# lv_2.net
KiCad netlist of a schematic drawn in Altium Designer
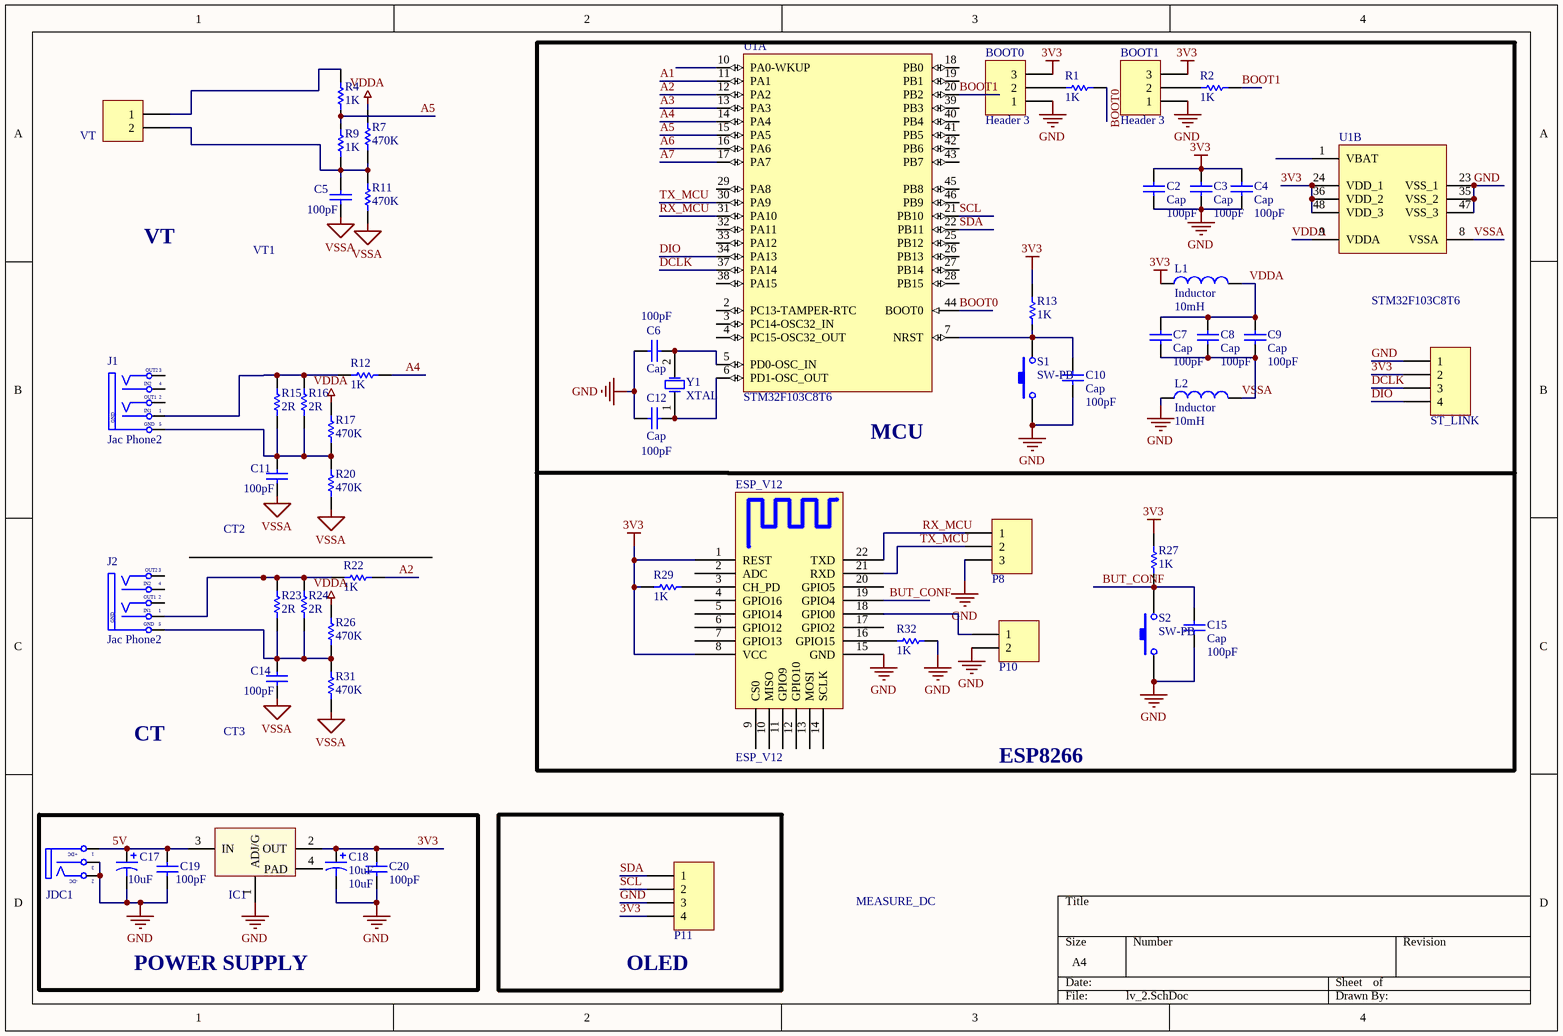
[diagram p0: lv_2.SchDoc]

(export (version "E")
  (design (tool "Eeschema 10.0.6"))
  (components
    (comp (ref "BOOT0")
      (value "Header 3")
      (footprint "JP3")
      (description "Header, 3-Pin")
      (fields (field (name "PUBLISHER") "Altium Limited"))
      (libsource (lib "Miscellaneous Connectors") (part "Header 3"))
    )
    (comp (ref "BOOT1")
      (value "Header 3")
      (footprint "JP3")
      (description "Header, 3-Pin")
      (fields (field (name "PUBLISHER") "Altium Limited"))
      (libsource (lib "Miscellaneous Connectors") (part "Header 3"))
    )
    (comp (ref "C2")
      (value "Cap")
      (footprint "CAP-SM-0603")
      (description "Capacitor")
      (fields (field (name "ALTIUM_VALUE") "100pF") (field (name "PUBLISHER") "Altium Limited"))
      (libsource (lib "Miscellaneous Devices") (part "Cap"))
    )
    (comp (ref "C3")
      (value "Cap")
      (footprint "CAP-SM-0603")
      (description "Capacitor")
      (fields (field (name "ALTIUM_VALUE") "100pF") (field (name "PUBLISHER") "Altium Limited"))
      (libsource (lib "Miscellaneous Devices") (part "Cap"))
    )
    (comp (ref "C4")
      (value "Cap")
      (footprint "CAP-SM-0603")
      (description "Capacitor")
      (fields (field (name "ALTIUM_VALUE") "100pF") (field (name "PUBLISHER") "Altium Limited"))
      (libsource (lib "Miscellaneous Devices") (part "Cap"))
    )
    (comp (ref "C5")
      (value "100pF")
      (footprint "CAP-SM-0603")
      (description "Capacitor")
      (fields (field (name "Comment") "Cap Non-Pol SMD"))
      (libsource (lib "PIF_Library") (part "Cap Non-Pol SMD"))
    )
    (comp (ref "C6")
      (value "Cap")
      (footprint "CAP-SM-0603")
      (description "Capacitor")
      (fields (field (name "ALTIUM_VALUE") "100pF") (field (name "PUBLISHER") "Altium Limited"))
      (libsource (lib "Miscellaneous Devices") (part "Cap"))
    )
    (comp (ref "C7")
      (value "Cap")
      (footprint "CAP-SM-0603")
      (description "Capacitor")
      (fields (field (name "ALTIUM_VALUE") "100pF") (field (name "PUBLISHER") "Altium Limited"))
      (libsource (lib "Miscellaneous Devices") (part "Cap"))
    )
    (comp (ref "C8")
      (value "Cap")
      (footprint "CAP-SM-0603")
      (description "Capacitor")
      (fields (field (name "ALTIUM_VALUE") "100pF") (field (name "PUBLISHER") "Altium Limited"))
      (libsource (lib "Miscellaneous Devices") (part "Cap"))
    )
    (comp (ref "C9")
      (value "Cap")
      (footprint "CAP-SM-0603")
      (description "Capacitor")
      (fields (field (name "ALTIUM_VALUE") "100pF") (field (name "PUBLISHER") "Altium Limited"))
      (libsource (lib "Miscellaneous Devices") (part "Cap"))
    )
    (comp (ref "C10")
      (value "Cap")
      (footprint "CAP-SM-0603")
      (description "Capacitor")
      (fields (field (name "ALTIUM_VALUE") "100pF") (field (name "PUBLISHER") "Altium Limited"))
      (libsource (lib "Miscellaneous Devices") (part "Cap"))
    )
    (comp (ref "C11")
      (value "100pF")
      (footprint "CAP-SM-0603")
      (description "Capacitor")
      (fields (field (name "Comment") "Cap Non-Pol SMD"))
      (libsource (lib "PIF_Library") (part "Cap Non-Pol SMD"))
    )
    (comp (ref "C12")
      (value "Cap")
      (footprint "CAP-SM-0603")
      (description "Capacitor")
      (fields (field (name "ALTIUM_VALUE") "100pF") (field (name "PUBLISHER") "Altium Limited"))
      (libsource (lib "Miscellaneous Devices") (part "Cap"))
    )
    (comp (ref "C14")
      (value "100pF")
      (footprint "CAP-SM-0603")
      (description "Capacitor")
      (fields (field (name "Comment") "Cap Non-Pol SMD"))
      (libsource (lib "PIF_Library") (part "Cap Non-Pol SMD"))
    )
    (comp (ref "C15")
      (value "Cap")
      (footprint "CAP-SM-0603")
      (description "Capacitor")
      (fields (field (name "ALTIUM_VALUE") "100pF") (field (name "PUBLISHER") "Altium Limited"))
      (libsource (lib "Miscellaneous Devices") (part "Cap"))
    )
    (comp (ref "C17")
      (value "10uF")
      (footprint "CP1/2")
      (description "Polarized Capacitor (Radial)")
      (fields (field (name "PUBLISHER") "Altium Limited"))
      (libsource (lib "Miscellaneous Devices") (part "Cap Pol1"))
    )
    (comp (ref "C18")
      (value "10uF")
      (footprint "CP1/2")
      (description "Polarized Capacitor (Radial)")
      (fields (field (name "ALTIUM_VALUE") "10uF") (field (name "PUBLISHER") "Altium Limited"))
      (libsource (lib "Miscellaneous Devices") (part "Cap Pol1"))
    )
    (comp (ref "C19")
      (value "100pF")
      (footprint "CAP-SM-0603")
      (description "Capacitor")
      (fields (field (name "Comment") "Cap Non-Pol SMD"))
      (libsource (lib "PIF_Library") (part "Cap Non-Pol SMD"))
    )
    (comp (ref "C20")
      (value "100pF")
      (footprint "CAP-SM-0603")
      (description "Capacitor")
      (fields (field (name "Comment") "Cap Non-Pol SMD"))
      (libsource (lib "PIF_Library") (part "Cap Non-Pol SMD"))
    )
    (comp (ref "ESP_V12")
      (value "ESP_V12")
      (footprint "ESP_12_E")
      (libsource (lib "espv12") (part "Component_1"))
    )
    (comp (ref "IC1")
      (value "LM1117")
      (footprint "SOT223-4N")
      (description "Available in 1.8V, 2.5V, 2.85V, 3.3V, 5V, and  Adjustable Versions")
      (libsource (lib "PIF_Library") (part "LM1117"))
    )
    (comp (ref "J1")
      (value "Jac Phone2")
      (footprint "JacPhone2")
      (description "Jac Phone Stereo")
      (fields (field (name "CREAT BY") "VanDungEvn@Gmail.com"))
      (libsource (lib "syhaunguyen") (part "Jac Phone2"))
    )
    (comp (ref "J2")
      (value "Jac Phone2")
      (footprint "JacPhone2")
      (description "Jac Phone Stereo")
      (fields (field (name "CREAT BY") "VanDungEvn@Gmail.com"))
      (libsource (lib "syhaunguyen") (part "Jac Phone2"))
    )
    (comp (ref "JDC1")
      (value "Jack DC")
      (footprint "DC-IN")
      (description "Jack DC input")
      (libsource (lib "PIF_Library") (part "Jack DC"))
    )
    (comp (ref "L1")
      (value "Inductor")
      (footprint "CAP-SM-0603")
      (fields (field (name "ALTIUM_VALUE") "10mH") (field (name "PUBLISHER") "Altium Limited"))
      (libsource (lib "Miscellaneous Devices") (part "Inductor"))
    )
    (comp (ref "L2")
      (value "Inductor")
      (footprint "CAP-SM-0603")
      (fields (field (name "ALTIUM_VALUE") "10mH") (field (name "PUBLISHER") "Altium Limited"))
      (libsource (lib "Miscellaneous Devices") (part "Inductor"))
    )
    (comp (ref "P8")
      (value "Header 3")
      (footprint "JP3")
      (description "Header, 3-Pin")
      (fields (field (name "PUBLISHER") "Altium Limited"))
      (libsource (lib "PIF_Library") (part "Header 3"))
    )
    (comp (ref "P10")
      (value "Header 2")
      (footprint "JP2")
      (description "Header, 2-Pin")
      (fields (field (name "PUBLISHER") "Altium Limited"))
      (libsource (lib "PIF_Library") (part "Header 2"))
    )
    (comp (ref "P11")
      (value "Header 4")
      (footprint "JP4")
      (description "Header, 4-Pin")
      (fields (field (name "PUBLISHER") "Altium Limited"))
      (libsource (lib "PIF_Library") (part "Header 4"))
    )
    (comp (ref "R1")
      (value "1K")
      (footprint "RES-SM-0603")
      (description "Resistor")
      (fields (field (name "Comment") "RESISTOR SMD"))
      (libsource (lib "PIF_Library") (part "RESISTOR SMD"))
    )
    (comp (ref "R2")
      (value "1K")
      (footprint "RES-SM-0603")
      (description "Resistor")
      (fields (field (name "Comment") "RESISTOR SMD"))
      (libsource (lib "PIF_Library") (part "RESISTOR SMD"))
    )
    (comp (ref "R4")
      (value "1K")
      (footprint "RES-SM-0603")
      (description "Resistor")
      (libsource (lib "PIF_Library") (part "RESISTOR SMD"))
    )
    (comp (ref "R7")
      (value "470K")
      (footprint "RES-SM-0603")
      (description "Resistor")
      (libsource (lib "PIF_Library") (part "RESISTOR SMD"))
    )
    (comp (ref "R9")
      (value "1K")
      (footprint "RES-SM-0603")
      (description "Resistor")
      (libsource (lib "PIF_Library") (part "RESISTOR SMD"))
    )
    (comp (ref "R11")
      (value "470K")
      (footprint "RES-SM-0603")
      (description "Resistor")
      (libsource (lib "PIF_Library") (part "RESISTOR SMD"))
    )
    (comp (ref "R12")
      (value "1K")
      (footprint "RES-SM-0603")
      (description "Resistor")
      (fields (field (name "Comment") "RESISTOR SMD"))
      (libsource (lib "PIF_Library") (part "RESISTOR SMD"))
    )
    (comp (ref "R13")
      (value "1K")
      (footprint "RES-SM-0603")
      (description "Resistor")
      (fields (field (name "Comment") "RESISTOR SMD"))
      (libsource (lib "PIF_Library") (part "RESISTOR SMD"))
    )
    (comp (ref "R15")
      (value "2R")
      (footprint "RES-SM-0603")
      (description "Resistor")
      (fields (field (name "Comment") "RESISTOR SMD"))
      (libsource (lib "PIF_Library") (part "RESISTOR SMD"))
    )
    (comp (ref "R16")
      (value "2R")
      (footprint "RES-SM-0603")
      (description "Resistor")
      (fields (field (name "Comment") "RESISTOR SMD"))
      (libsource (lib "PIF_Library") (part "RESISTOR SMD"))
    )
    (comp (ref "R17")
      (value "470K")
      (footprint "RES-SM-0603")
      (description "Resistor")
      (fields (field (name "Comment") "RESISTOR SMD"))
      (libsource (lib "PIF_Library") (part "RESISTOR SMD"))
    )
    (comp (ref "R20")
      (value "470K")
      (footprint "RES-SM-0603")
      (description "Resistor")
      (fields (field (name "Comment") "RESISTOR SMD"))
      (libsource (lib "PIF_Library") (part "RESISTOR SMD"))
    )
    (comp (ref "R22")
      (value "1K")
      (footprint "RES-SM-0603")
      (description "Resistor")
      (fields (field (name "Comment") "RESISTOR SMD"))
      (libsource (lib "PIF_Library") (part "RESISTOR SMD"))
    )
    (comp (ref "R23")
      (value "2R")
      (footprint "RES-SM-0603")
      (description "Resistor")
      (fields (field (name "Comment") "RESISTOR SMD"))
      (libsource (lib "PIF_Library") (part "RESISTOR SMD"))
    )
    (comp (ref "R24")
      (value "2R")
      (footprint "RES-SM-0603")
      (description "Resistor")
      (fields (field (name "Comment") "RESISTOR SMD"))
      (libsource (lib "PIF_Library") (part "RESISTOR SMD"))
    )
    (comp (ref "R26")
      (value "470K")
      (footprint "RES-SM-0603")
      (description "Resistor")
      (fields (field (name "Comment") "RESISTOR SMD"))
      (libsource (lib "PIF_Library") (part "RESISTOR SMD"))
    )
    (comp (ref "R27")
      (value "1K")
      (footprint "RES-SM-0603")
      (description "Resistor")
      (fields (field (name "Comment") "RESISTOR SMD"))
      (libsource (lib "PIF_Library") (part "RESISTOR SMD"))
    )
    (comp (ref "R29")
      (value "1K")
      (footprint "RES-SM-0603")
      (description "Resistor")
      (fields (field (name "Comment") "RESISTOR SMD"))
      (libsource (lib "PIF_Library") (part "RESISTOR SMD"))
    )
    (comp (ref "R31")
      (value "470K")
      (footprint "RES-SM-0603")
      (description "Resistor")
      (fields (field (name "Comment") "RESISTOR SMD"))
      (libsource (lib "PIF_Library") (part "RESISTOR SMD"))
    )
    (comp (ref "R32")
      (value "1K")
      (footprint "RES-SM-0603")
      (description "Resistor")
      (fields (field (name "Comment") "RESISTOR SMD"))
      (libsource (lib "PIF_Library") (part "RESISTOR SMD"))
    )
    (comp (ref "S1")
      (value "SW-PB")
      (footprint "Tact SW 4 pin")
      (description "Switch")
      (fields (field (name "PUBLISHER") "Altium Limited"))
      (libsource (lib "Miscellaneous Devices") (part "SW-PB"))
    )
    (comp (ref "S2")
      (value "SW-PB")
      (footprint "Tact SW 4 pin")
      (description "Switch")
      (fields (field (name "PUBLISHER") "Altium Limited"))
      (libsource (lib "Miscellaneous Devices") (part "SW-PB"))
    )
    (comp (ref "ST_LINK")
      (value "Header 4")
      (footprint "JP4")
      (description "Header, 4-Pin")
      (fields (field (name "PUBLISHER") "Altium Limited"))
      (libsource (lib "PIF_Schematic_Lib") (part "Header 4"))
    )
    (comp (ref "U1")
      (value "STM32F103C8T6")
      (footprint "STM-LQFP48_L")
      (libsource (lib "STMicroelectronics STM32 F1") (part "STM32F103C8T6"))
    )
    (comp (ref "VT")
      (value "Domino 2")
      (footprint "DOMINO 2- 5mm")
      (description "Domino, 2-Pin")
      (fields (field (name "PUBLISHER") "Altium Limited"))
      (libsource (lib "PIF_Library") (part "Domino 2"))
    )
    (comp (ref "Y1")
      (value "XTAL")
      (footprint "XT2")
      (description "Crystal Oscillator")
      (fields (field (name "PUBLISHER") "Altium Limited"))
      (libsource (lib "Miscellaneous Devices") (part "XTAL"))
    )
  )
  (nets
    (net (code "1") (name "/5V") (class "Default")
      (node (ref "C17") (pin "1") (pinfunction "1_1") (pintype "passive"))
      (node (ref "C19") (pin "2") (pinfunction "2_2") (pintype "passive"))
      (node (ref "IC1") (pin "3") (pinfunction "IN_3") (pintype "passive"))
      (node (ref "JDC1") (pin "1") (pinfunction "T_1") (pintype "passive"))
    )
    (net (code "2") (name "/A1") (class "Default")
      (node (ref "U1") (pin "11") (pinfunction "PA1_11") (pintype "bidirectional"))
    )
    (net (code "3") (name "/A2") (class "Default")
      (node (ref "R22") (pin "1") (pinfunction "1_1") (pintype "passive"))
      (node (ref "U1") (pin "12") (pinfunction "PA2_12") (pintype "bidirectional"))
    )
    (net (code "4") (name "/A3") (class "Default")
      (node (ref "U1") (pin "13") (pinfunction "PA3_13") (pintype "bidirectional"))
    )
    (net (code "5") (name "/A4") (class "Default")
      (node (ref "R12") (pin "1") (pinfunction "1_1") (pintype "passive"))
      (node (ref "U1") (pin "14") (pinfunction "PA4_14") (pintype "bidirectional"))
    )
    (net (code "6") (name "/A5") (class "Default")
      (node (ref "R4") (pin "1") (pinfunction "1_1") (pintype "passive"))
      (node (ref "R9") (pin "2") (pinfunction "2_2") (pintype "passive"))
      (node (ref "U1") (pin "15") (pinfunction "PA5_15") (pintype "bidirectional"))
    )
    (net (code "7") (name "/A6") (class "Default")
      (node (ref "U1") (pin "16") (pinfunction "PA6_16") (pintype "bidirectional"))
    )
    (net (code "8") (name "/A7") (class "Default")
      (node (ref "U1") (pin "17") (pinfunction "PA7_17") (pintype "bidirectional"))
    )
    (net (code "9") (name "/BOOT0") (class "Default")
      (node (ref "R1") (pin "1") (pinfunction "1_1") (pintype "passive"))
      (node (ref "U1") (pin "44") (pinfunction "BOOT0_44") (pintype "input"))
    )
    (net (code "10") (name "/BOOT1") (class "Default")
      (node (ref "R2") (pin "1") (pinfunction "1_1") (pintype "passive"))
      (node (ref "U1") (pin "20") (pinfunction "PB2_20") (pintype "bidirectional"))
    )
    (net (code "11") (name "/BUT_CONF") (class "Default")
      (node (ref "C15") (pin "2") (pinfunction "2_2") (pintype "passive"))
      (node (ref "ESP_V12") (pin "19") (pinfunction "GPIO4_19") (pintype "passive"))
      (node (ref "R27") (pin "2") (pinfunction "2_2") (pintype "passive"))
      (node (ref "S2") (pin "2") (pinfunction "2_2") (pintype "passive"))
    )
    (net (code "12") (name "/DCLK") (class "Default")
      (node (ref "ST_LINK") (pin "3") (pinfunction "3_3") (pintype "passive"))
      (node (ref "U1") (pin "37") (pinfunction "PA14_37") (pintype "bidirectional"))
    )
    (net (code "13") (name "/DIO") (class "Default")
      (node (ref "ST_LINK") (pin "4") (pinfunction "4_4") (pintype "passive"))
      (node (ref "U1") (pin "34") (pinfunction "PA13_34") (pintype "bidirectional"))
    )
    (net (code "14") (name "/RX_MCU") (class "Default")
      (node (ref "ESP_V12") (pin "22") (pinfunction "TXD_22") (pintype "passive"))
      (node (ref "P8") (pin "1") (pinfunction "1_1") (pintype "passive"))
      (node (ref "U1") (pin "31") (pinfunction "PA10_31") (pintype "bidirectional"))
    )
    (net (code "15") (name "/SCL") (class "Default")
      (node (ref "P11") (pin "2") (pinfunction "2_2") (pintype "passive"))
      (node (ref "U1") (pin "21") (pinfunction "PB10_21") (pintype "bidirectional"))
    )
    (net (code "16") (name "/SDA") (class "Default")
      (node (ref "P11") (pin "1") (pinfunction "1_1") (pintype "passive"))
      (node (ref "U1") (pin "22") (pinfunction "PB11_22") (pintype "bidirectional"))
    )
    (net (code "17") (name "/TX_MCU") (class "Default")
      (node (ref "ESP_V12") (pin "21") (pinfunction "RXD_21") (pintype "passive"))
      (node (ref "P8") (pin "2") (pinfunction "2_2") (pintype "passive"))
      (node (ref "U1") (pin "30") (pinfunction "PA9_30") (pintype "bidirectional"))
    )
    (net (code "18") (name "3V3") (class "Default")
      (node (ref "BOOT0") (pin "3") (pinfunction "3_3") (pintype "passive"))
      (node (ref "BOOT1") (pin "3") (pinfunction "3_3") (pintype "passive"))
      (node (ref "C18") (pin "1") (pinfunction "1_1") (pintype "passive"))
      (node (ref "C2") (pin "2") (pinfunction "2_2") (pintype "passive"))
      (node (ref "C20") (pin "2") (pinfunction "2_2") (pintype "passive"))
      (node (ref "C3") (pin "2") (pinfunction "2_2") (pintype "passive"))
      (node (ref "C4") (pin "2") (pinfunction "2_2") (pintype "passive"))
      (node (ref "ESP_V12") (pin "1") (pinfunction "REST_1") (pintype "passive"))
      (node (ref "ESP_V12") (pin "8") (pinfunction "VCC_8") (pintype "passive"))
      (node (ref "IC1") (pin "2") (pinfunction "OUT_2") (pintype "passive"))
      (node (ref "L1") (pin "1") (pinfunction "1_1") (pintype "passive"))
      (node (ref "P11") (pin "4") (pinfunction "4_4") (pintype "passive"))
      (node (ref "R13") (pin "1") (pinfunction "1_1") (pintype "passive"))
      (node (ref "R27") (pin "1") (pinfunction "1_1") (pintype "passive"))
      (node (ref "R29") (pin "1") (pinfunction "1_1") (pintype "passive"))
      (node (ref "ST_LINK") (pin "2") (pinfunction "2_2") (pintype "passive"))
      (node (ref "U1") (pin "24") (pinfunction "VDD_1_24") (pintype "power_in"))
      (node (ref "U1") (pin "36") (pinfunction "VDD_2_36") (pintype "power_in"))
      (node (ref "U1") (pin "48") (pinfunction "VDD_3_48") (pintype "power_in"))
    )
    (net (code "19") (name "GND") (class "Default")
      (node (ref "BOOT0") (pin "1") (pinfunction "1_1") (pintype "passive"))
      (node (ref "BOOT1") (pin "1") (pinfunction "1_1") (pintype "passive"))
      (node (ref "C10") (pin "1") (pinfunction "1_1") (pintype "passive"))
      (node (ref "C12") (pin "1") (pinfunction "1_1") (pintype "passive"))
      (node (ref "C15") (pin "1") (pinfunction "1_1") (pintype "passive"))
      (node (ref "C17") (pin "2") (pinfunction "2_2") (pintype "passive"))
      (node (ref "C18") (pin "2") (pinfunction "2_2") (pintype "passive"))
      (node (ref "C19") (pin "1") (pinfunction "1_1") (pintype "passive"))
      (node (ref "C2") (pin "1") (pinfunction "1_1") (pintype "passive"))
      (node (ref "C20") (pin "1") (pinfunction "1_1") (pintype "passive"))
      (node (ref "C3") (pin "1") (pinfunction "1_1") (pintype "passive"))
      (node (ref "C4") (pin "1") (pinfunction "1_1") (pintype "passive"))
      (node (ref "C6") (pin "1") (pinfunction "1_1") (pintype "passive"))
      (node (ref "ESP_V12") (pin "15") (pinfunction "GND_15") (pintype "passive"))
      (node (ref "IC1") (pin "1") (pinfunction "ADJ/G_1") (pintype "passive"))
      (node (ref "JDC1") (pin "2") (pinfunction "TN_2") (pintype "passive"))
      (node (ref "JDC1") (pin "3") (pinfunction "S_3") (pintype "power_in"))
      (node (ref "L2") (pin "1") (pinfunction "1_1") (pintype "passive"))
      (node (ref "P10") (pin "2") (pinfunction "2_2") (pintype "passive"))
      (node (ref "P11") (pin "3") (pinfunction "3_3") (pintype "passive"))
      (node (ref "P8") (pin "3") (pinfunction "3_3") (pintype "passive"))
      (node (ref "R32") (pin "2") (pinfunction "2_2") (pintype "passive"))
      (node (ref "S1") (pin "1") (pinfunction "1_1") (pintype "passive"))
      (node (ref "S2") (pin "1") (pinfunction "1_1") (pintype "passive"))
      (node (ref "ST_LINK") (pin "1") (pinfunction "1_1") (pintype "passive"))
      (node (ref "U1") (pin "23") (pinfunction "VSS_1_23") (pintype "power_in"))
      (node (ref "U1") (pin "35") (pinfunction "VSS_2_35") (pintype "power_in"))
      (node (ref "U1") (pin "47") (pinfunction "VSS_3_47") (pintype "power_in"))
    )
    (net (code "20") (name "Net-(BOOT0-Pad2)") (class "Default")
      (node (ref "BOOT0") (pin "2") (pinfunction "2_2") (pintype "passive"))
      (node (ref "R1") (pin "2") (pinfunction "2_2") (pintype "passive"))
    )
    (net (code "21") (name "Net-(BOOT1-Pad2)") (class "Default")
      (node (ref "BOOT1") (pin "2") (pinfunction "2_2") (pintype "passive"))
      (node (ref "R2") (pin "2") (pinfunction "2_2") (pintype "passive"))
    )
    (net (code "22") (name "Net-(C5-Pad2)") (class "Default")
      (node (ref "C5") (pin "2") (pinfunction "2_2") (pintype "passive"))
      (node (ref "R11") (pin "2") (pinfunction "2_2") (pintype "passive"))
      (node (ref "R7") (pin "1") (pinfunction "1_1") (pintype "passive"))
      (node (ref "R9") (pin "1") (pinfunction "1_1") (pintype "passive"))
      (node (ref "VT") (pin "2") (pinfunction "2_2") (pintype "passive"))
    )
    (net (code "23") (name "Net-(ESP_V12-CH_PD)") (class "Default")
      (node (ref "ESP_V12") (pin "3") (pinfunction "CH_PD_3") (pintype "passive"))
      (node (ref "R29") (pin "2") (pinfunction "2_2") (pintype "passive"))
    )
    (net (code "24") (name "Net-(ESP_V12-GPIO0)") (class "Default")
      (node (ref "ESP_V12") (pin "18") (pinfunction "GPIO0_18") (pintype "passive"))
      (node (ref "P10") (pin "1") (pinfunction "1_1") (pintype "passive"))
    )
    (net (code "25") (name "Net-(ESP_V12-GPIO15)") (class "Default")
      (node (ref "ESP_V12") (pin "16") (pinfunction "GPIO15_16") (pintype "passive"))
      (node (ref "R32") (pin "1") (pinfunction "1_1") (pintype "passive"))
    )
    (net (code "26") (name "Net-(J1-GND)") (class "Default")
      (node (ref "C11") (pin "2") (pinfunction "2_2") (pintype "passive"))
      (node (ref "J1") (pin "5") (pinfunction "GND_5") (pintype "passive"))
      (node (ref "R15") (pin "1") (pinfunction "1_1") (pintype "passive"))
      (node (ref "R16") (pin "1") (pinfunction "1_1") (pintype "passive"))
      (node (ref "R17") (pin "1") (pinfunction "1_1") (pintype "passive"))
      (node (ref "R20") (pin "2") (pinfunction "2_2") (pintype "passive"))
    )
    (net (code "27") (name "Net-(J1-S1-Pad1)") (class "Default")
      (node (ref "J1") (pin "1") (pinfunction "S1_1") (pintype "power_in"))
      (node (ref "R12") (pin "2") (pinfunction "2_2") (pintype "passive"))
      (node (ref "R15") (pin "2") (pinfunction "2_2") (pintype "passive"))
      (node (ref "R16") (pin "2") (pinfunction "2_2") (pintype "passive"))
    )
    (net (code "28") (name "Net-(J2-GND)") (class "Default")
      (node (ref "C14") (pin "2") (pinfunction "2_2") (pintype "passive"))
      (node (ref "J2") (pin "5") (pinfunction "GND_5") (pintype "passive"))
      (node (ref "R23") (pin "1") (pinfunction "1_1") (pintype "passive"))
      (node (ref "R24") (pin "1") (pinfunction "1_1") (pintype "passive"))
      (node (ref "R26") (pin "1") (pinfunction "1_1") (pintype "passive"))
      (node (ref "R31") (pin "2") (pinfunction "2_2") (pintype "passive"))
    )
    (net (code "29") (name "Net-(J2-S1-Pad1)") (class "Default")
      (node (ref "J2") (pin "1") (pinfunction "S1_1") (pintype "power_in"))
      (node (ref "R22") (pin "2") (pinfunction "2_2") (pintype "passive"))
      (node (ref "R23") (pin "2") (pinfunction "2_2") (pintype "passive"))
      (node (ref "R24") (pin "2") (pinfunction "2_2") (pintype "passive"))
    )
    (net (code "30") (name "Net-(R4-Pad2)") (class "Default")
      (node (ref "R4") (pin "2") (pinfunction "2_2") (pintype "passive"))
      (node (ref "VT") (pin "1") (pinfunction "1_1") (pintype "passive"))
    )
    (net (code "31") (name "Net-(U1A-NRST)") (class "Default")
      (node (ref "C10") (pin "2") (pinfunction "2_2") (pintype "passive"))
      (node (ref "R13") (pin "2") (pinfunction "2_2") (pintype "passive"))
      (node (ref "S1") (pin "2") (pinfunction "2_2") (pintype "passive"))
      (node (ref "U1") (pin "7") (pinfunction "NRST_7") (pintype "bidirectional"))
    )
    (net (code "32") (name "Net-(U1A-PD0-OSC_IN)") (class "Default")
      (node (ref "C6") (pin "2") (pinfunction "2_2") (pintype "passive"))
      (node (ref "U1") (pin "5") (pinfunction "PD0-OSC_IN_5") (pintype "bidirectional"))
      (node (ref "Y1") (pin "2") (pinfunction "OSC2_2") (pintype "passive"))
    )
    (net (code "33") (name "Net-(U1A-PD1-OSC_OUT)") (class "Default")
      (node (ref "C12") (pin "2") (pinfunction "2_2") (pintype "passive"))
      (node (ref "U1") (pin "6") (pinfunction "PD1-OSC_OUT_6") (pintype "bidirectional"))
      (node (ref "Y1") (pin "1") (pinfunction "OSC1_1") (pintype "passive"))
    )
    (net (code "34") (name "VDDA") (class "Default")
      (node (ref "C7") (pin "2") (pinfunction "2_2") (pintype "passive"))
      (node (ref "C8") (pin "2") (pinfunction "2_2") (pintype "passive"))
      (node (ref "C9") (pin "2") (pinfunction "2_2") (pintype "passive"))
      (node (ref "L1") (pin "2") (pinfunction "2_2") (pintype "passive"))
      (node (ref "R17") (pin "2") (pinfunction "2_2") (pintype "passive"))
      (node (ref "R26") (pin "2") (pinfunction "2_2") (pintype "passive"))
      (node (ref "R7") (pin "2") (pinfunction "2_2") (pintype "passive"))
      (node (ref "U1") (pin "9") (pinfunction "VDDA_9") (pintype "power_in"))
    )
    (net (code "35") (name "VSSA") (class "Default")
      (node (ref "C11") (pin "1") (pinfunction "1_1") (pintype "passive"))
      (node (ref "C14") (pin "1") (pinfunction "1_1") (pintype "passive"))
      (node (ref "C5") (pin "1") (pinfunction "1_1") (pintype "passive"))
      (node (ref "C7") (pin "1") (pinfunction "1_1") (pintype "passive"))
      (node (ref "C8") (pin "1") (pinfunction "1_1") (pintype "passive"))
      (node (ref "C9") (pin "1") (pinfunction "1_1") (pintype "passive"))
      (node (ref "L2") (pin "2") (pinfunction "2_2") (pintype "passive"))
      (node (ref "R11") (pin "1") (pinfunction "1_1") (pintype "passive"))
      (node (ref "R20") (pin "1") (pinfunction "1_1") (pintype "passive"))
      (node (ref "R31") (pin "1") (pinfunction "1_1") (pintype "passive"))
      (node (ref "U1") (pin "8") (pinfunction "VSSA_8") (pintype "power_in"))
    )
    (net (code "36") (name "unconnected-(ESP_V12-ADC-Pad2)") (class "Default")
      (node (ref "ESP_V12") (pin "2") (pinfunction "ADC_2") (pintype "passive"))
    )
    (net (code "37") (name "unconnected-(ESP_V12-CS0-Pad9)") (class "Default")
      (node (ref "ESP_V12") (pin "9") (pinfunction "CS0_9") (pintype "passive"))
    )
    (net (code "38") (name "unconnected-(ESP_V12-GPIO2-Pad17)") (class "Default")
      (node (ref "ESP_V12") (pin "17") (pinfunction "GPIO2_17") (pintype "passive"))
    )
    (net (code "39") (name "unconnected-(ESP_V12-GPIO5-Pad20)") (class "Default")
      (node (ref "ESP_V12") (pin "20") (pinfunction "GPIO5_20") (pintype "passive"))
    )
    (net (code "40") (name "unconnected-(ESP_V12-GPIO9-Pad11)") (class "Default")
      (node (ref "ESP_V12") (pin "11") (pinfunction "GPIO9_11") (pintype "passive"))
    )
    (net (code "41") (name "unconnected-(ESP_V12-GPIO10-Pad12)") (class "Default")
      (node (ref "ESP_V12") (pin "12") (pinfunction "GPIO10_12") (pintype "passive"))
    )
    (net (code "42") (name "unconnected-(ESP_V12-GPIO12-Pad6)") (class "Default")
      (node (ref "ESP_V12") (pin "6") (pinfunction "GPIO12_6") (pintype "passive"))
    )
    (net (code "43") (name "unconnected-(ESP_V12-GPIO13-Pad7)") (class "Default")
      (node (ref "ESP_V12") (pin "7") (pinfunction "GPIO13_7") (pintype "passive"))
    )
    (net (code "44") (name "unconnected-(ESP_V12-GPIO14-Pad5)") (class "Default")
      (node (ref "ESP_V12") (pin "5") (pinfunction "GPIO14_5") (pintype "passive"))
    )
    (net (code "45") (name "unconnected-(ESP_V12-GPIO16-Pad4)") (class "Default")
      (node (ref "ESP_V12") (pin "4") (pinfunction "GPIO16_4") (pintype "passive"))
    )
    (net (code "46") (name "unconnected-(ESP_V12-MISO-Pad10)") (class "Default")
      (node (ref "ESP_V12") (pin "10") (pinfunction "MISO_10") (pintype "passive"))
    )
    (net (code "47") (name "unconnected-(ESP_V12-MOSI-Pad13)") (class "Default")
      (node (ref "ESP_V12") (pin "13") (pinfunction "MOSI_13") (pintype "passive"))
    )
    (net (code "48") (name "unconnected-(ESP_V12-SCLK-Pad14)") (class "Default")
      (node (ref "ESP_V12") (pin "14") (pinfunction "SCLK_14") (pintype "passive"))
    )
    (net (code "49") (name "unconnected-(IC1-PAD-Pad4)") (class "Default")
      (node (ref "IC1") (pin "4") (pinfunction "PAD_4") (pintype "passive"))
    )
    (net (code "50") (name "unconnected-(J1-S-Pad4)") (class "Default")
      (node (ref "J1") (pin "4") (pinfunction "S_4") (pintype "power_in"))
    )
    (net (code "51") (name "unconnected-(J1-S1-Pad2)") (class "Default")
      (node (ref "J1") (pin "2") (pinfunction "S1_2") (pintype "passive"))
    )
    (net (code "52") (name "unconnected-(J1-TN-Pad3)") (class "Default")
      (node (ref "J1") (pin "3") (pinfunction "TN_3") (pintype "passive"))
    )
    (net (code "53") (name "unconnected-(J2-S-Pad4)") (class "Default")
      (node (ref "J2") (pin "4") (pinfunction "S_4") (pintype "power_in"))
    )
    (net (code "54") (name "unconnected-(J2-S1-Pad2)") (class "Default")
      (node (ref "J2") (pin "2") (pinfunction "S1_2") (pintype "passive"))
    )
    (net (code "55") (name "unconnected-(J2-TN-Pad3)") (class "Default")
      (node (ref "J2") (pin "3") (pinfunction "TN_3") (pintype "passive"))
    )
    (net (code "56") (name "unconnected-(U1A-PA0-WKUP-Pad10)") (class "Default")
      (node (ref "U1") (pin "10") (pinfunction "PA0-WKUP_10") (pintype "bidirectional"))
    )
    (net (code "57") (name "unconnected-(U1A-PA8-Pad29)") (class "Default")
      (node (ref "U1") (pin "29") (pinfunction "PA8_29") (pintype "bidirectional"))
    )
    (net (code "58") (name "unconnected-(U1A-PA11-Pad32)") (class "Default")
      (node (ref "U1") (pin "32") (pinfunction "PA11_32") (pintype "bidirectional"))
    )
    (net (code "59") (name "unconnected-(U1A-PA12-Pad33)") (class "Default")
      (node (ref "U1") (pin "33") (pinfunction "PA12_33") (pintype "bidirectional"))
    )
    (net (code "60") (name "unconnected-(U1A-PA15-Pad38)") (class "Default")
      (node (ref "U1") (pin "38") (pinfunction "PA15_38") (pintype "bidirectional"))
    )
    (net (code "61") (name "unconnected-(U1A-PB0-Pad18)") (class "Default")
      (node (ref "U1") (pin "18") (pinfunction "PB0_18") (pintype "bidirectional"))
    )
    (net (code "62") (name "unconnected-(U1A-PB1-Pad19)") (class "Default")
      (node (ref "U1") (pin "19") (pinfunction "PB1_19") (pintype "bidirectional"))
    )
    (net (code "63") (name "unconnected-(U1A-PB3-Pad39)") (class "Default")
      (node (ref "U1") (pin "39") (pinfunction "PB3_39") (pintype "bidirectional"))
    )
    (net (code "64") (name "unconnected-(U1A-PB4-Pad40)") (class "Default")
      (node (ref "U1") (pin "40") (pinfunction "PB4_40") (pintype "bidirectional"))
    )
    (net (code "65") (name "unconnected-(U1A-PB5-Pad41)") (class "Default")
      (node (ref "U1") (pin "41") (pinfunction "PB5_41") (pintype "bidirectional"))
    )
    (net (code "66") (name "unconnected-(U1A-PB6-Pad42)") (class "Default")
      (node (ref "U1") (pin "42") (pinfunction "PB6_42") (pintype "bidirectional"))
    )
    (net (code "67") (name "unconnected-(U1A-PB7-Pad43)") (class "Default")
      (node (ref "U1") (pin "43") (pinfunction "PB7_43") (pintype "bidirectional"))
    )
    (net (code "68") (name "unconnected-(U1A-PB8-Pad45)") (class "Default")
      (node (ref "U1") (pin "45") (pinfunction "PB8_45") (pintype "bidirectional"))
    )
    (net (code "69") (name "unconnected-(U1A-PB9-Pad46)") (class "Default")
      (node (ref "U1") (pin "46") (pinfunction "PB9_46") (pintype "bidirectional"))
    )
    (net (code "70") (name "unconnected-(U1A-PB12-Pad25)") (class "Default")
      (node (ref "U1") (pin "25") (pinfunction "PB12_25") (pintype "bidirectional"))
    )
    (net (code "71") (name "unconnected-(U1A-PB13-Pad26)") (class "Default")
      (node (ref "U1") (pin "26") (pinfunction "PB13_26") (pintype "bidirectional"))
    )
    (net (code "72") (name "unconnected-(U1A-PB14-Pad27)") (class "Default")
      (node (ref "U1") (pin "27") (pinfunction "PB14_27") (pintype "bidirectional"))
    )
    (net (code "73") (name "unconnected-(U1A-PB15-Pad28)") (class "Default")
      (node (ref "U1") (pin "28") (pinfunction "PB15_28") (pintype "bidirectional"))
    )
    (net (code "74") (name "unconnected-(U1A-PC13-TAMPER-RTC-Pad2)") (class "Default")
      (node (ref "U1") (pin "2") (pinfunction "PC13-TAMPER-RTC_2") (pintype "bidirectional"))
    )
    (net (code "75") (name "unconnected-(U1A-PC14-OSC32_IN-Pad3)") (class "Default")
      (node (ref "U1") (pin "3") (pinfunction "PC14-OSC32_IN_3") (pintype "bidirectional"))
    )
    (net (code "76") (name "unconnected-(U1A-PC15-OSC32_OUT-Pad4)") (class "Default")
      (node (ref "U1") (pin "4") (pinfunction "PC15-OSC32_OUT_4") (pintype "bidirectional"))
    )
    (net (code "77") (name "unconnected-(U1B-VBAT-Pad1)") (class "Default")
      (node (ref "U1") (pin "1") (pinfunction "VBAT_1") (pintype "power_in"))
    )
  )
)
